# initial-commit-01.net
KiCad netlist of a schematic drawn in EAGLE
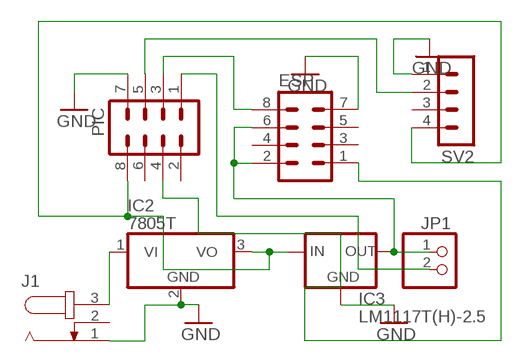
[diagram p0: schematic, sheet 1]

(export (version "E")
  (design (tool "Eeschema 10.0.6"))
  (components
    (comp (ref "ESP")
      (value "MA04-2")
      (footprint "eagle-import:MA04-2")
      (libsource (lib "eagle-import") (part "MA04-2"))
    )
    (comp (ref "IC2")
      (value "7805T")
      (footprint "eagle-import:TO220H")
      (libsource (lib "eagle-import") (part "78T05"))
    )
    (comp (ref "IC3")
      (value "LM1117T(H)-2.5")
      (footprint "eagle-import:TO220H")
      (fields (field (name "MF") "Texas Instruments") (field (name "MPN") "LM1117T-2.5"))
      (libsource (lib "eagle-import") (part "LM1117?-T(H)2.5"))
    )
    (comp (ref "J1")
      (value "JACK-PLUG1")
      (footprint "eagle-import:SPC4078")
      (libsource (lib "eagle-import") (part "JACK-PLUG1"))
    )
    (comp (ref "JP1")
      (value "PINHD-1X2")
      (footprint "eagle-import:1X02")
      (libsource (lib "eagle-import") (part "PINHD-1X2"))
    )
    (comp (ref "PIC")
      (value "MA04-2")
      (footprint "eagle-import:MA04-2")
      (libsource (lib "eagle-import") (part "MA04-2"))
    )
    (comp (ref "SV2")
      (value "MA04-1")
      (footprint "eagle-import:MA04-1")
      (libsource (lib "eagle-import") (part "MA04-1"))
    )
  )
  (nets
    (net (code "1") (name "GND") (class "Default")
      (node (ref "ESP") (pin "7") (pinfunction "7_7") (pintype "passive"))
      (node (ref "IC2") (pin "2") (pinfunction "GND_2") (pintype "passive"))
      (node (ref "IC3") (pin "1") (pinfunction "GND_1") (pintype "input"))
      (node (ref "J1") (pin "1") (pinfunction "1_1") (pintype "passive"))
      (node (ref "PIC") (pin "7") (pinfunction "7_7") (pintype "passive"))
      (node (ref "SV2") (pin "1") (pinfunction "1_1") (pintype "passive"))
    )
    (net (code "2") (name "Net-(ESP-Pad1)") (class "Default")
      (node (ref "ESP") (pin "1") (pinfunction "1_1") (pintype "passive"))
      (node (ref "PIC") (pin "4") (pinfunction "4_4") (pintype "passive"))
    )
    (net (code "3") (name "Net-(ESP-Pad8)") (class "Default")
      (node (ref "ESP") (pin "8") (pinfunction "8_8") (pintype "passive"))
      (node (ref "PIC") (pin "3") (pinfunction "3_3") (pintype "passive"))
    )
    (net (code "4") (name "Net-(IC2-VI)") (class "Default")
      (node (ref "IC2") (pin "1") (pinfunction "VI_1") (pintype "input"))
      (node (ref "J1") (pin "3") (pinfunction "3_3") (pintype "passive"))
    )
    (net (code "5") (name "Net-(IC2-VO)") (class "Default")
      (node (ref "IC2") (pin "3") (pinfunction "VO_3") (pintype "passive"))
      (node (ref "IC3") (pin "3") (pinfunction "IN_3") (pintype "input"))
      (node (ref "PIC") (pin "8") (pinfunction "8_8") (pintype "passive"))
      (node (ref "SV2") (pin "4") (pinfunction "4_4") (pintype "passive"))
    )
    (net (code "6") (name "Net-(IC3-OUT)") (class "Default")
      (node (ref "ESP") (pin "2") (pinfunction "2_2") (pintype "passive"))
      (node (ref "ESP") (pin "6") (pinfunction "6_6") (pintype "passive"))
      (node (ref "IC3") (pin "2") (pinfunction "OUT_2") (pintype "passive"))
      (node (ref "JP1") (pin "1") (pinfunction "1_1") (pintype "passive"))
    )
    (net (code "7") (name "Net-(JP1-Pad2)") (class "Default")
      (node (ref "JP1") (pin "2") (pinfunction "2_2") (pintype "passive"))
      (node (ref "PIC") (pin "1") (pinfunction "1_1") (pintype "passive"))
    )
    (net (code "8") (name "Net-(PIC-Pad5)") (class "Default")
      (node (ref "PIC") (pin "5") (pinfunction "5_5") (pintype "passive"))
      (node (ref "SV2") (pin "2") (pinfunction "2_2") (pintype "passive"))
    )
    (net (code "9") (name "unconnected-(ESP-Pad3)") (class "Default")
      (node (ref "ESP") (pin "3") (pinfunction "3_3") (pintype "passive"))
    )
    (net (code "10") (name "unconnected-(ESP-Pad4)") (class "Default")
      (node (ref "ESP") (pin "4") (pinfunction "4_4") (pintype "passive"))
    )
    (net (code "11") (name "unconnected-(ESP-Pad5)") (class "Default")
      (node (ref "ESP") (pin "5") (pinfunction "5_5") (pintype "passive"))
    )
    (net (code "12") (name "unconnected-(J1-Pad2)") (class "Default")
      (node (ref "J1") (pin "2") (pinfunction "2_2") (pintype "passive"))
    )
    (net (code "13") (name "unconnected-(PIC-Pad2)") (class "Default")
      (node (ref "PIC") (pin "2") (pinfunction "2_2") (pintype "passive"))
    )
    (net (code "14") (name "unconnected-(PIC-Pad6)") (class "Default")
      (node (ref "PIC") (pin "6") (pinfunction "6_6") (pintype "passive"))
    )
    (net (code "15") (name "unconnected-(SV2-Pad3)") (class "Default")
      (node (ref "SV2") (pin "3") (pinfunction "3_3") (pintype "passive"))
    )
  )
)
